# BMI160_SCHEMATIC.net
KiCad netlist of a schematic drawn in EAGLE
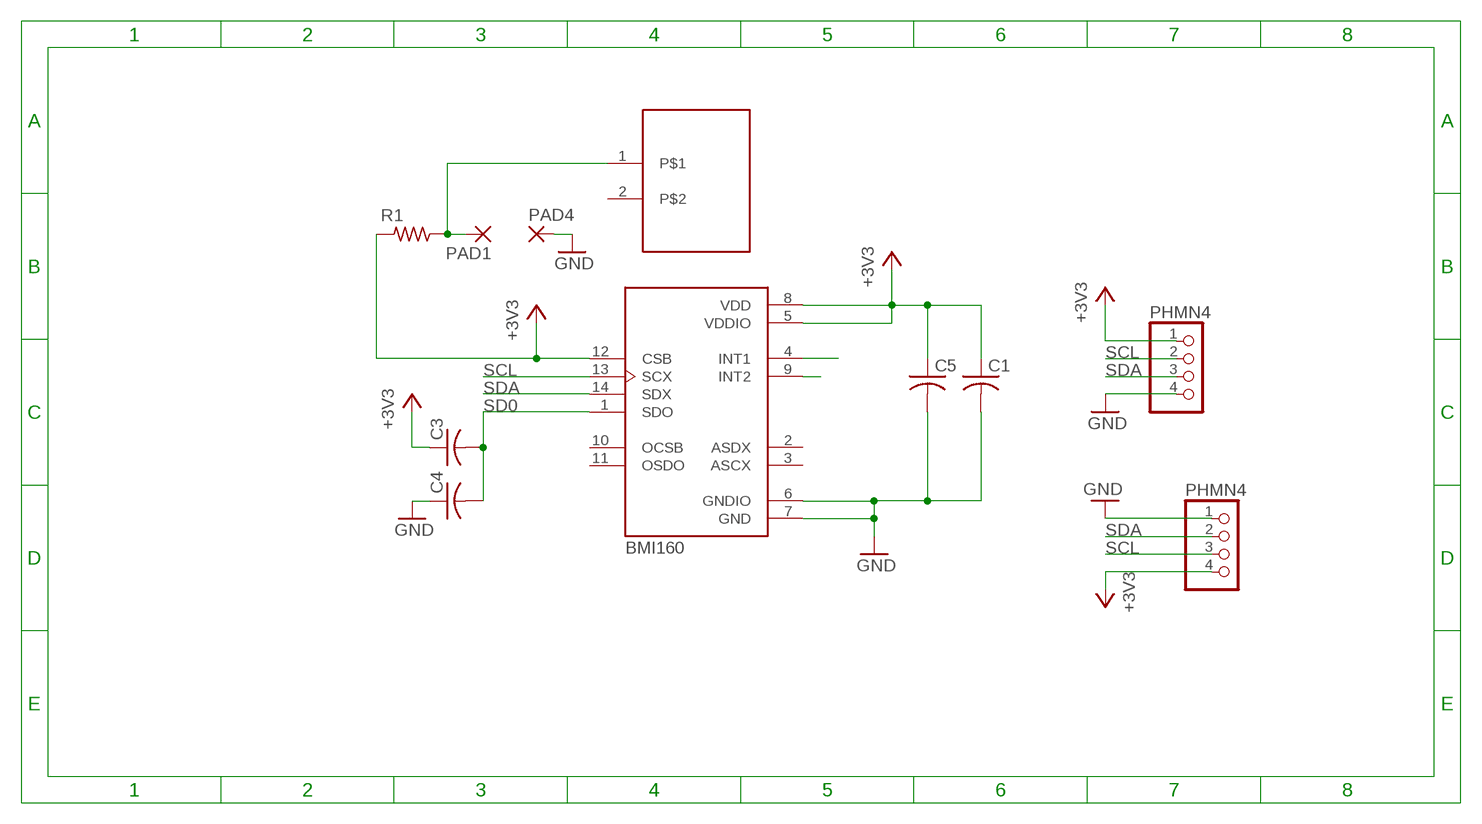
[diagram p0: schematic, sheet 1]

(export (version "E")
  (design (tool "Eeschema 10.0.6"))
  (components
    (comp (ref "C1")
      (value "C-USC0805")
      (footprint "eagle-import:C0805")
      (libsource (lib "eagle-import") (part "C-USC0805"))
    )
    (comp (ref "C3")
      (value "C-USC0805")
      (footprint "eagle-import:C0805")
      (libsource (lib "eagle-import") (part "C-USC0805"))
    )
    (comp (ref "C4")
      (value "C-USC0805")
      (footprint "eagle-import:C0805")
      (libsource (lib "eagle-import") (part "C-USC0805"))
    )
    (comp (ref "C5")
      (value "C-USC0805")
      (footprint "eagle-import:C0805")
      (libsource (lib "eagle-import") (part "C-USC0805"))
    )
    (comp (ref "PAD1")
      (value "WIREPADSMD1,27-254")
      (footprint "eagle-import:SMD1,27-2,54")
      (libsource (lib "eagle-import") (part "WIREPADSMD1,27-254"))
    )
    (comp (ref "PAD4")
      (value "WIREPADSMD1,27-254")
      (footprint "eagle-import:SMD1,27-2,54")
      (libsource (lib "eagle-import") (part "WIREPADSMD1,27-254"))
    )
    (comp (ref "R1")
      (value "CRCW08050000Z0EA")
      (footprint "eagle-import:RES_0805")
      (fields
        (field (name "DIGIKEY_PART_NUMBER") "541-0.0ATR-ND")
        (field (name "MANUFACTURER") "Vishay Dale")
        (field (name "CREATED_BY") "PCBLayout.com")
      )
      (libsource (lib "eagle-import") (part "CRCW08050000Z0EA"))
    )
    (comp (ref "U$1")
      (value "PHMN4")
      (footprint "eagle-import:1X04")
      (libsource (lib "eagle-import") (part "PHMN4"))
    )
    (comp (ref "U$2")
      (value "PHMN4")
      (footprint "eagle-import:1X04")
      (libsource (lib "eagle-import") (part "PHMN4"))
    )
    (comp (ref "U$3")
      (value "PHMN4-21X02")
      (footprint "eagle-import:HDRV2W64P254_1X2_1016X508X838B")
      (libsource (lib "eagle-import") (part "PHMN4-21X02"))
    )
    (comp (ref "U1")
      (value "BMI160")
      (footprint "eagle-import:PQFN50P300X250X88-14N")
      (fields (field (name "MF") "Bosch"))
      (libsource (lib "eagle-import") (part "BMI160"))
    )
  )
  (nets
    (net (code "1") (name "+3V3") (class "Default")
      (node (ref "C1") (pin "1") (pinfunction "1_1") (pintype "passive"))
      (node (ref "C3") (pin "1") (pinfunction "1_1") (pintype "passive"))
      (node (ref "C5") (pin "1") (pinfunction "1_1") (pintype "passive"))
      (node (ref "R1") (pin "2") (pinfunction "2_2") (pintype "passive"))
      (node (ref "U$1") (pin "1") (pinfunction "1_1") (pintype "passive"))
      (node (ref "U$2") (pin "4") (pinfunction "4_4") (pintype "passive"))
      (node (ref "U1") (pin "12") (pinfunction "CSB_12") (pintype "input"))
      (node (ref "U1") (pin "5") (pinfunction "VDDIO_5") (pintype "power_in"))
      (node (ref "U1") (pin "8") (pinfunction "VDD_8") (pintype "power_in"))
    )
    (net (code "2") (name "/SCL") (class "Default")
      (node (ref "U$1") (pin "2") (pinfunction "2_2") (pintype "passive"))
      (node (ref "U$2") (pin "3") (pinfunction "3_3") (pintype "passive"))
      (node (ref "U1") (pin "13") (pinfunction "SCX_13") (pintype "input"))
    )
    (net (code "3") (name "/SD0") (class "Default")
      (node (ref "C3") (pin "2") (pinfunction "2_2") (pintype "passive"))
      (node (ref "C4") (pin "2") (pinfunction "2_2") (pintype "passive"))
      (node (ref "U1") (pin "1") (pinfunction "SDO_1") (pintype "bidirectional"))
    )
    (net (code "4") (name "/SDA") (class "Default")
      (node (ref "U$1") (pin "3") (pinfunction "3_3") (pintype "passive"))
      (node (ref "U$2") (pin "2") (pinfunction "2_2") (pintype "passive"))
      (node (ref "U1") (pin "14") (pinfunction "SDX_14") (pintype "bidirectional"))
    )
    (net (code "5") (name "GND") (class "Default")
      (node (ref "C1") (pin "2") (pinfunction "2_2") (pintype "passive"))
      (node (ref "C4") (pin "1") (pinfunction "1_1") (pintype "passive"))
      (node (ref "C5") (pin "2") (pinfunction "2_2") (pintype "passive"))
      (node (ref "PAD4") (pin "1") (pinfunction "P_1") (pintype "passive"))
      (node (ref "U$1") (pin "4") (pinfunction "4_4") (pintype "passive"))
      (node (ref "U$2") (pin "1") (pinfunction "1_1") (pintype "passive"))
      (node (ref "U1") (pin "6") (pinfunction "GNDIO_6") (pintype "power_in"))
      (node (ref "U1") (pin "7") (pinfunction "GND_7") (pintype "power_in"))
    )
    (net (code "6") (name "Net-(PAD1-P)") (class "Default")
      (node (ref "PAD1") (pin "1") (pinfunction "P_1") (pintype "passive"))
      (node (ref "R1") (pin "1") (pinfunction "1_1") (pintype "passive"))
      (node (ref "U$3") (pin "1") (pinfunction "P$1_1") (pintype "bidirectional"))
    )
    (net (code "7") (name "unconnected-(U$3-P$2-Pad2)") (class "Default")
      (node (ref "U$3") (pin "2") (pinfunction "P$2_2") (pintype "bidirectional"))
    )
    (net (code "8") (name "unconnected-(U1-ASCX-Pad3)") (class "Default")
      (node (ref "U1") (pin "3") (pinfunction "ASCX_3") (pintype "output"))
    )
    (net (code "9") (name "unconnected-(U1-ASDX-Pad2)") (class "Default")
      (node (ref "U1") (pin "2") (pinfunction "ASDX_2") (pintype "bidirectional"))
    )
    (net (code "10") (name "unconnected-(U1-INT1-Pad4)") (class "Default")
      (node (ref "U1") (pin "4") (pinfunction "INT1_4") (pintype "bidirectional"))
    )
    (net (code "11") (name "unconnected-(U1-INT2-Pad9)") (class "Default")
      (node (ref "U1") (pin "9") (pinfunction "INT2_9") (pintype "bidirectional"))
    )
    (net (code "12") (name "unconnected-(U1-OCSB-Pad10)") (class "Default")
      (node (ref "U1") (pin "10") (pinfunction "OCSB_10") (pintype "bidirectional"))
    )
    (net (code "13") (name "unconnected-(U1-OSDO-Pad11)") (class "Default")
      (node (ref "U1") (pin "11") (pinfunction "OSDO_11") (pintype "bidirectional"))
    )
  )
)
